# CON_ATA_25.net
KiCad netlist of a schematic drawn in Altium Designer
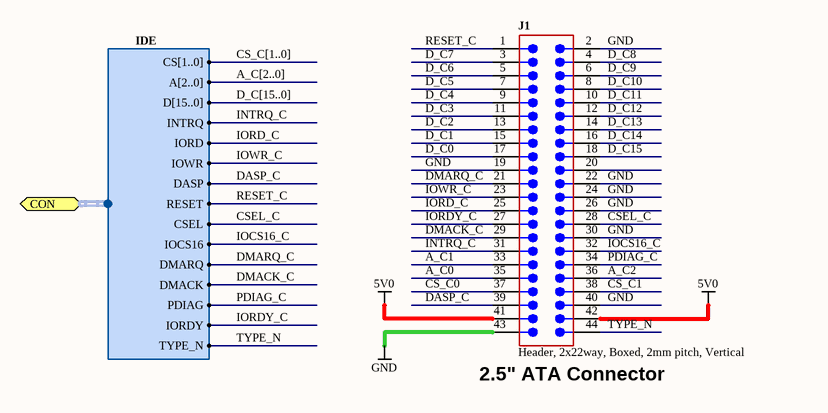
[diagram p0: CON_ATA_25.SchDoc]

(export (version "E")
  (design (tool "Eeschema 10.0.6"))
  (components
    (comp (ref "J1")
      (value "Header, 2x22way, Boxed, 2mm pitch, Vertical")
      (footprint "HDR2X22-2mm")
      (libsource (lib "AltiumDesignLibrary") (part "CON-IDC-2x22-M-STR-2mm"))
    )
  )
  (nets
    (net (code "2") (name "/A_C0") (class "Default")
      (node (ref "J1") (pin "35") (pinfunction "35_35") (pintype "passive"))
    )
    (net (code "3") (name "/A_C1") (class "Default")
      (node (ref "J1") (pin "33") (pinfunction "33_33") (pintype "passive"))
    )
    (net (code "4") (name "/A_C2") (class "Default")
      (node (ref "J1") (pin "36") (pinfunction "36_36") (pintype "passive"))
    )
    (net (code "6") (name "/CSEL_C") (class "Default")
      (node (ref "J1") (pin "28") (pinfunction "28_28") (pintype "passive"))
    )
    (net (code "7") (name "/CS_C0") (class "Default")
      (node (ref "J1") (pin "37") (pinfunction "37_37") (pintype "passive"))
    )
    (net (code "8") (name "/CS_C1") (class "Default")
      (node (ref "J1") (pin "38") (pinfunction "38_38") (pintype "passive"))
    )
    (net (code "10") (name "/DASP_C") (class "Default")
      (node (ref "J1") (pin "39") (pinfunction "39_39") (pintype "passive"))
    )
    (net (code "11") (name "/DMACK_C") (class "Default")
      (node (ref "J1") (pin "29") (pinfunction "29_29") (pintype "passive"))
    )
    (net (code "12") (name "/DMARQ_C") (class "Default")
      (node (ref "J1") (pin "21") (pinfunction "21_21") (pintype "passive"))
    )
    (net (code "13") (name "/D_C0") (class "Default")
      (node (ref "J1") (pin "17") (pinfunction "17_17") (pintype "passive"))
    )
    (net (code "14") (name "/D_C1") (class "Default")
      (node (ref "J1") (pin "15") (pinfunction "15_15") (pintype "passive"))
    )
    (net (code "15") (name "/D_C2") (class "Default")
      (node (ref "J1") (pin "13") (pinfunction "13_13") (pintype "passive"))
    )
    (net (code "16") (name "/D_C3") (class "Default")
      (node (ref "J1") (pin "11") (pinfunction "11_11") (pintype "passive"))
    )
    (net (code "17") (name "/D_C4") (class "Default")
      (node (ref "J1") (pin "9") (pinfunction "9_9") (pintype "passive"))
    )
    (net (code "18") (name "/D_C5") (class "Default")
      (node (ref "J1") (pin "7") (pinfunction "7_7") (pintype "passive"))
    )
    (net (code "19") (name "/D_C6") (class "Default")
      (node (ref "J1") (pin "5") (pinfunction "5_5") (pintype "passive"))
    )
    (net (code "20") (name "/D_C7") (class "Default")
      (node (ref "J1") (pin "3") (pinfunction "3_3") (pintype "passive"))
    )
    (net (code "21") (name "/D_C8") (class "Default")
      (node (ref "J1") (pin "4") (pinfunction "4_4") (pintype "passive"))
    )
    (net (code "22") (name "/D_C9") (class "Default")
      (node (ref "J1") (pin "6") (pinfunction "6_6") (pintype "passive"))
    )
    (net (code "23") (name "/D_C10") (class "Default")
      (node (ref "J1") (pin "8") (pinfunction "8_8") (pintype "passive"))
    )
    (net (code "24") (name "/D_C11") (class "Default")
      (node (ref "J1") (pin "10") (pinfunction "10_10") (pintype "passive"))
    )
    (net (code "25") (name "/D_C12") (class "Default")
      (node (ref "J1") (pin "12") (pinfunction "12_12") (pintype "passive"))
    )
    (net (code "26") (name "/D_C13") (class "Default")
      (node (ref "J1") (pin "14") (pinfunction "14_14") (pintype "passive"))
    )
    (net (code "27") (name "/D_C14") (class "Default")
      (node (ref "J1") (pin "16") (pinfunction "16_16") (pintype "passive"))
    )
    (net (code "28") (name "/D_C15") (class "Default")
      (node (ref "J1") (pin "18") (pinfunction "18_18") (pintype "passive"))
    )
    (net (code "30") (name "/INTRQ_C") (class "Default")
      (node (ref "J1") (pin "31") (pinfunction "31_31") (pintype "passive"))
    )
    (net (code "31") (name "/IOCS16_C") (class "Default")
      (node (ref "J1") (pin "32") (pinfunction "32_32") (pintype "passive"))
    )
    (net (code "32") (name "/IORDY_C") (class "Default")
      (node (ref "J1") (pin "27") (pinfunction "27_27") (pintype "passive"))
    )
    (net (code "33") (name "/IORD_C") (class "Default")
      (node (ref "J1") (pin "25") (pinfunction "25_25") (pintype "passive"))
    )
    (net (code "34") (name "/IOWR_C") (class "Default")
      (node (ref "J1") (pin "23") (pinfunction "23_23") (pintype "passive"))
    )
    (net (code "35") (name "/PDIAG_C") (class "Default")
      (node (ref "J1") (pin "34") (pinfunction "34_34") (pintype "passive"))
    )
    (net (code "36") (name "/RESET_C") (class "Default")
      (node (ref "J1") (pin "1") (pinfunction "1_1") (pintype "passive"))
    )
    (net (code "37") (name "/TYPE_N") (class "Default")
      (node (ref "J1") (pin "44") (pinfunction "44_44") (pintype "passive"))
    )
    (net (code "39") (name "5V0") (class "Default")
      (node (ref "J1") (pin "41") (pinfunction "41_41") (pintype "passive"))
      (node (ref "J1") (pin "42") (pinfunction "42_42") (pintype "passive"))
    )
    (net (code "40") (name "GND") (class "Default")
      (node (ref "J1") (pin "19") (pinfunction "19_19") (pintype "passive"))
      (node (ref "J1") (pin "2") (pinfunction "2_2") (pintype "passive"))
      (node (ref "J1") (pin "22") (pinfunction "22_22") (pintype "passive"))
      (node (ref "J1") (pin "24") (pinfunction "24_24") (pintype "passive"))
      (node (ref "J1") (pin "26") (pinfunction "26_26") (pintype "passive"))
      (node (ref "J1") (pin "30") (pinfunction "30_30") (pintype "passive"))
      (node (ref "J1") (pin "40") (pinfunction "40_40") (pintype "passive"))
      (node (ref "J1") (pin "43") (pinfunction "43_43") (pintype "passive"))
    )
    (net (code "41") (name "unconnected-(J1-Pad20)") (class "Default")
      (node (ref "J1") (pin "20") (pinfunction "20_20") (pintype "passive"))
    )
  )
)
